# Sensor.net
KiCad netlist of a schematic drawn in Altium Designer
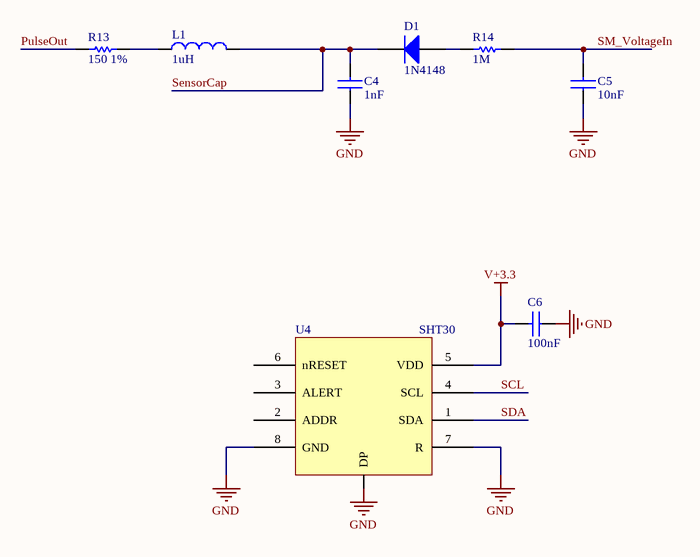
[diagram p0: Sensor.SchDoc]

(export (version "E")
  (design (tool "Eeschema 10.0.6"))
  (components
    (comp (ref "C4")
      (value "1nF")
      (footprint "0603")
      (fields (field (name "MANUFACTURER") "AVX") (field (name "MANUFACTURER PART NUMBER") "04023A101JAT2A"))
      (libsource (lib "PASSIVE_082011") (part "C_0402"))
    )
    (comp (ref "C5")
      (value "10nF")
      (footprint "0603")
      (fields (field (name "MANUFACTURER") "AVX") (field (name "MANUFACTURER PART NUMBER") "04023A101JAT2A"))
      (libsource (lib "PASSIVE_082011") (part "C_0402"))
    )
    (comp (ref "C6")
      (value "100nF")
      (footprint "0603")
      (fields (field (name "MANUFACTURER") "AVX") (field (name "MANUFACTURER PART NUMBER") "04023A101JAT2A"))
      (libsource (lib "PASSIVE_082011") (part "C_0402"))
    )
    (comp (ref "D1")
      (value "1N4148")
      (footprint "D1810")
      (description "Default Diode")
      (fields (field (name "PUBLISHER") "Altium Limited"))
      (libsource (lib "Miscellaneous Devices") (part "Diode"))
    )
    (comp (ref "L1")
      (value "1uH")
      (footprint "1210")
      (description "Inductor")
      (fields (field (name "PUBLISHER") "Altium Limited"))
      (libsource (lib "Miscellaneous Devices") (part "Inductor"))
    )
    (comp (ref "R13")
      (value "150 1%")
      (footprint "0603")
      (description "Semiconductor Resistor")
      (fields (field (name "PUBLISHER") "Altium Limited"))
      (libsource (lib "Miscellaneous Devices") (part "Res Semi"))
    )
    (comp (ref "R14")
      (value "1M")
      (footprint "0603")
      (description "Semiconductor Resistor")
      (fields (field (name "PUBLISHER") "Altium Limited"))
      (libsource (lib "Miscellaneous Devices") (part "Res Semi"))
    )
    (comp (ref "U4")
      (value "SHT30")
      (footprint "QFN50P250X250X100_HS-9N")
      (libsource (lib "Schlib1") (part "SHT3x"))
    )
  )
  (nets
    (net (code "1") (name "/PulseOut") (class "Default")
      (node (ref "R13") (pin "1") (pinfunction "1_1") (pintype "passive"))
    )
    (net (code "2") (name "/SCL") (class "Default")
      (node (ref "U4") (pin "4") (pinfunction "SCL_4") (pintype "passive"))
    )
    (net (code "3") (name "/SDA") (class "Default")
      (node (ref "U4") (pin "1") (pinfunction "SDA_1") (pintype "passive"))
    )
    (net (code "4") (name "/SM_VoltageIn") (class "Default")
      (node (ref "C5") (pin "2") (pinfunction "2_2") (pintype "passive"))
      (node (ref "R14") (pin "1") (pinfunction "1_1") (pintype "passive"))
    )
    (net (code "5") (name "/SensorCap") (class "Default")
      (node (ref "C4") (pin "2") (pinfunction "2_2") (pintype "passive"))
      (node (ref "D1") (pin "2") (pinfunction "K_2") (pintype "passive"))
      (node (ref "L1") (pin "2") (pinfunction "2_2") (pintype "passive"))
    )
    (net (code "6") (name "GND") (class "Default")
      (node (ref "C4") (pin "1") (pinfunction "1_1") (pintype "passive"))
      (node (ref "C5") (pin "1") (pinfunction "1_1") (pintype "passive"))
      (node (ref "C6") (pin "1") (pinfunction "1_1") (pintype "passive"))
      (node (ref "U4") (pin "0") (pinfunction "DP_0") (pintype "passive"))
      (node (ref "U4") (pin "7") (pinfunction "R_7") (pintype "passive"))
      (node (ref "U4") (pin "8") (pinfunction "GND_8") (pintype "passive"))
    )
    (net (code "7") (name "Net-(D1-A)") (class "Default")
      (node (ref "D1") (pin "1") (pinfunction "A_1") (pintype "passive"))
      (node (ref "R14") (pin "2") (pinfunction "2_2") (pintype "passive"))
    )
    (net (code "8") (name "Net-(L1-Pad1)") (class "Default")
      (node (ref "L1") (pin "1") (pinfunction "1_1") (pintype "passive"))
      (node (ref "R13") (pin "2") (pinfunction "2_2") (pintype "passive"))
    )
    (net (code "9") (name "V+3.3") (class "Default")
      (node (ref "C6") (pin "2") (pinfunction "2_2") (pintype "passive"))
      (node (ref "U4") (pin "5") (pinfunction "VDD_5") (pintype "passive"))
    )
    (net (code "10") (name "unconnected-(U4-ADDR-Pad2)") (class "Default")
      (node (ref "U4") (pin "2") (pinfunction "ADDR_2") (pintype "passive"))
    )
    (net (code "11") (name "unconnected-(U4-ALERT-Pad3)") (class "Default")
      (node (ref "U4") (pin "3") (pinfunction "ALERT_3") (pintype "passive"))
    )
    (net (code "12") (name "unconnected-(U4-nRESET-Pad6)") (class "Default")
      (node (ref "U4") (pin "6") (pinfunction "nRESET_6") (pintype "passive"))
    )
  )
)
